# Aux_Power_Board.net
KiCad netlist of a schematic drawn in EAGLE
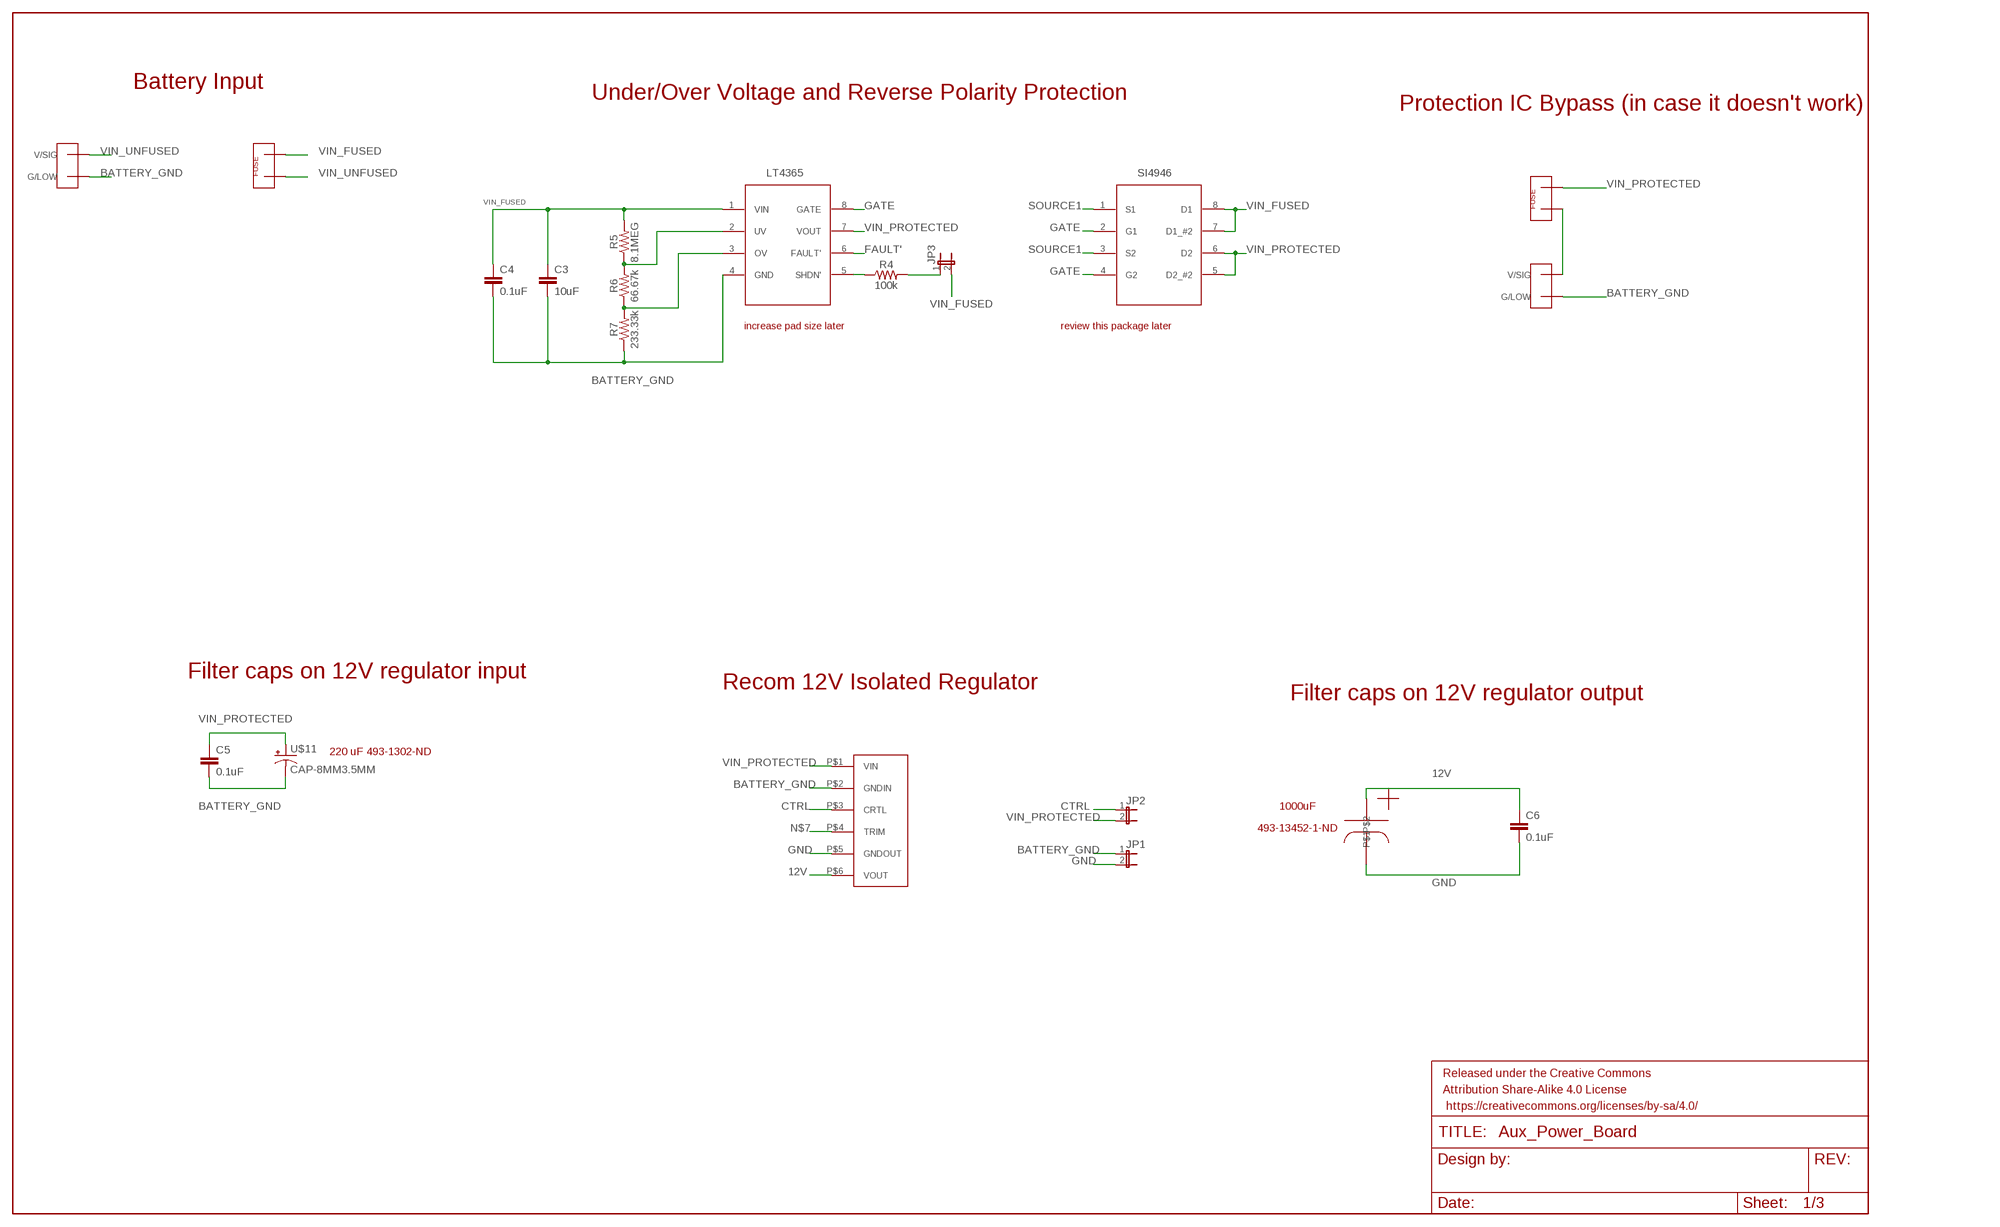
[diagram p0: schematic, sheet 1]
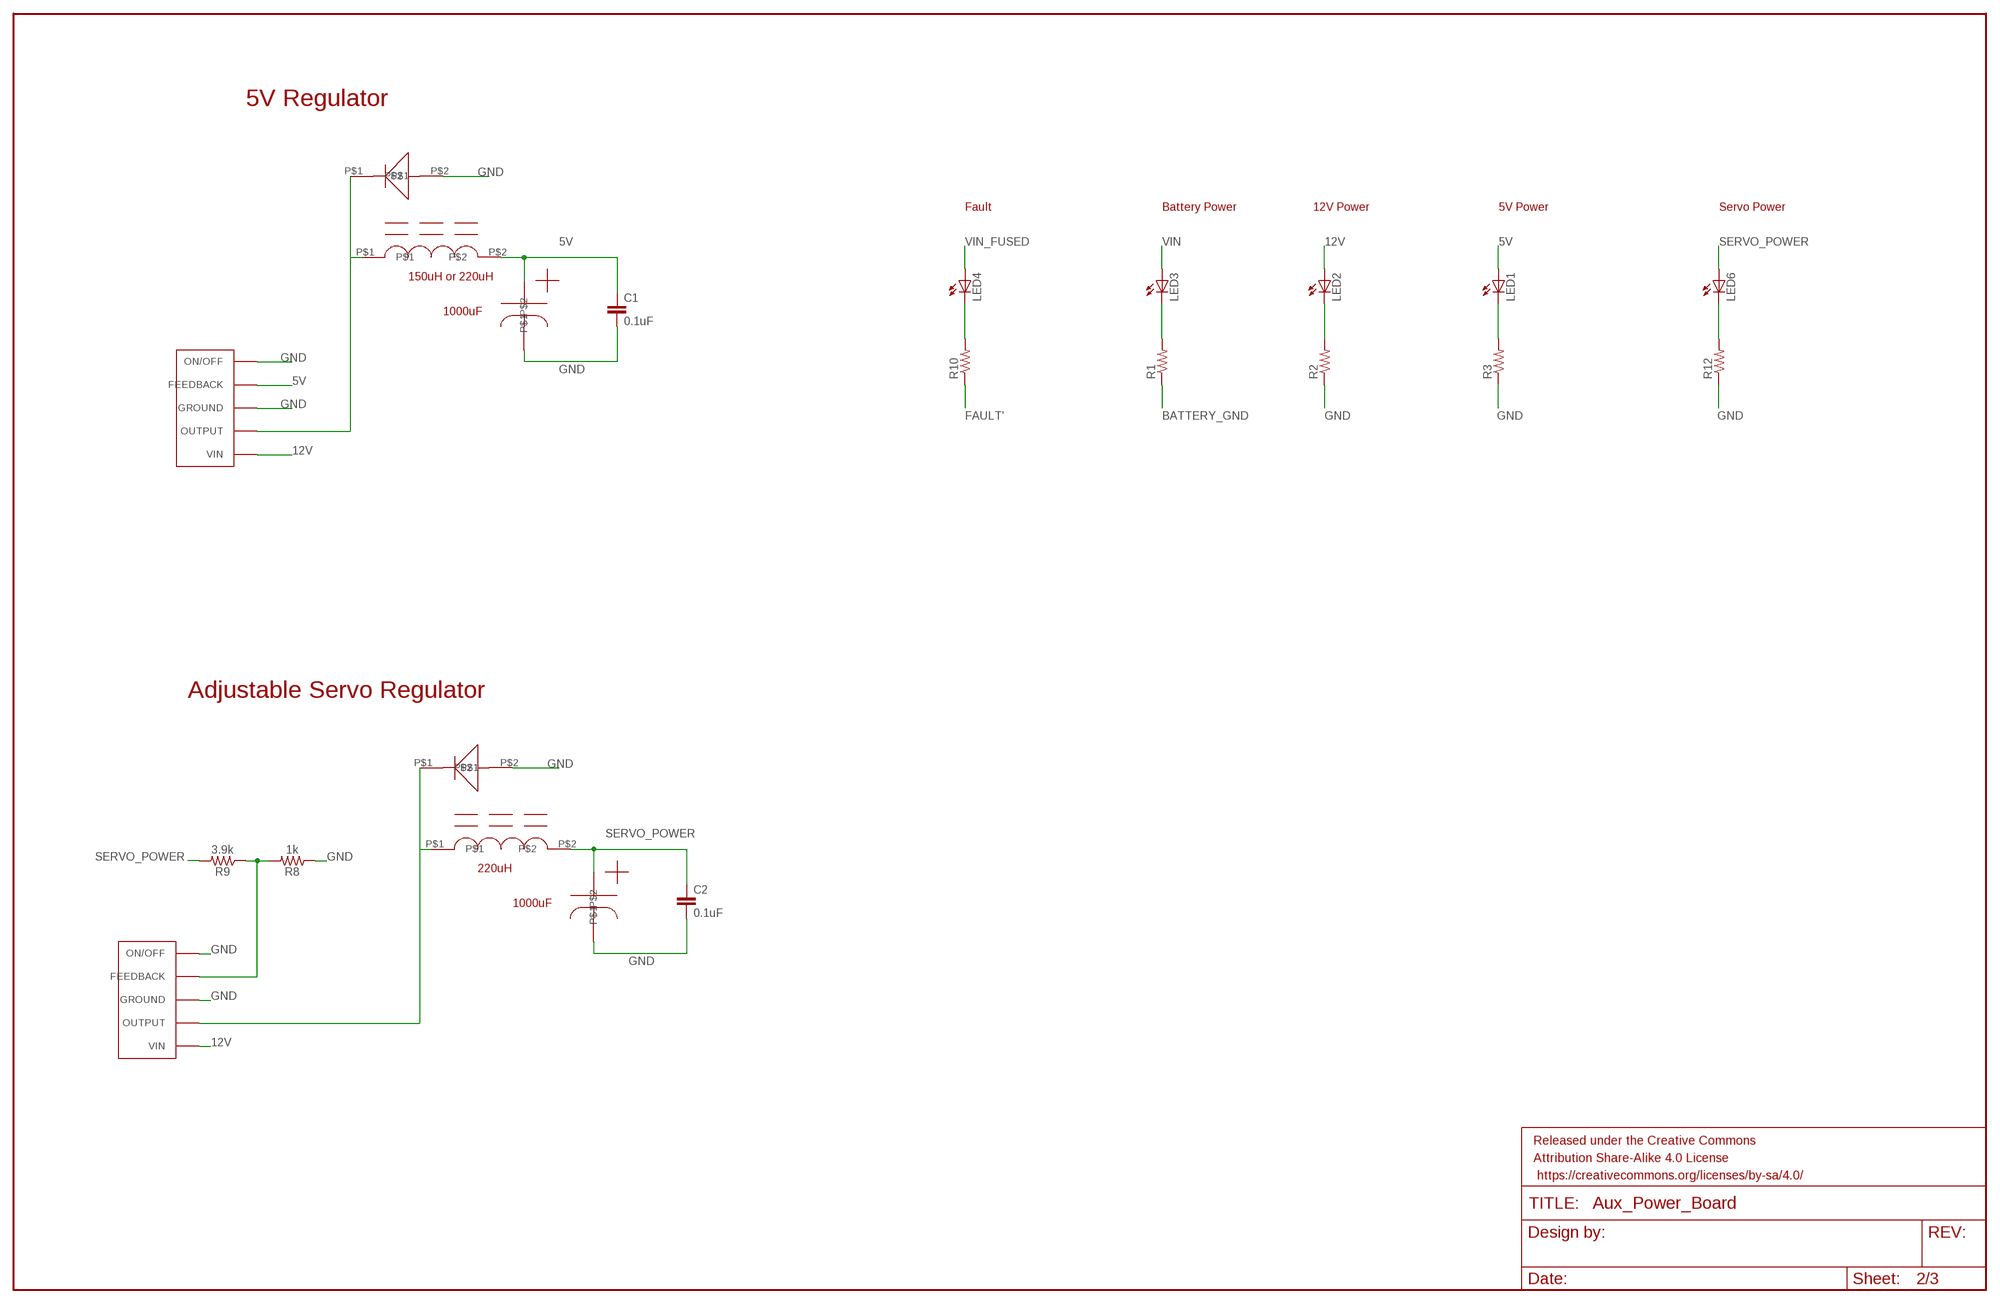
[diagram p1: schematic, sheet 2]
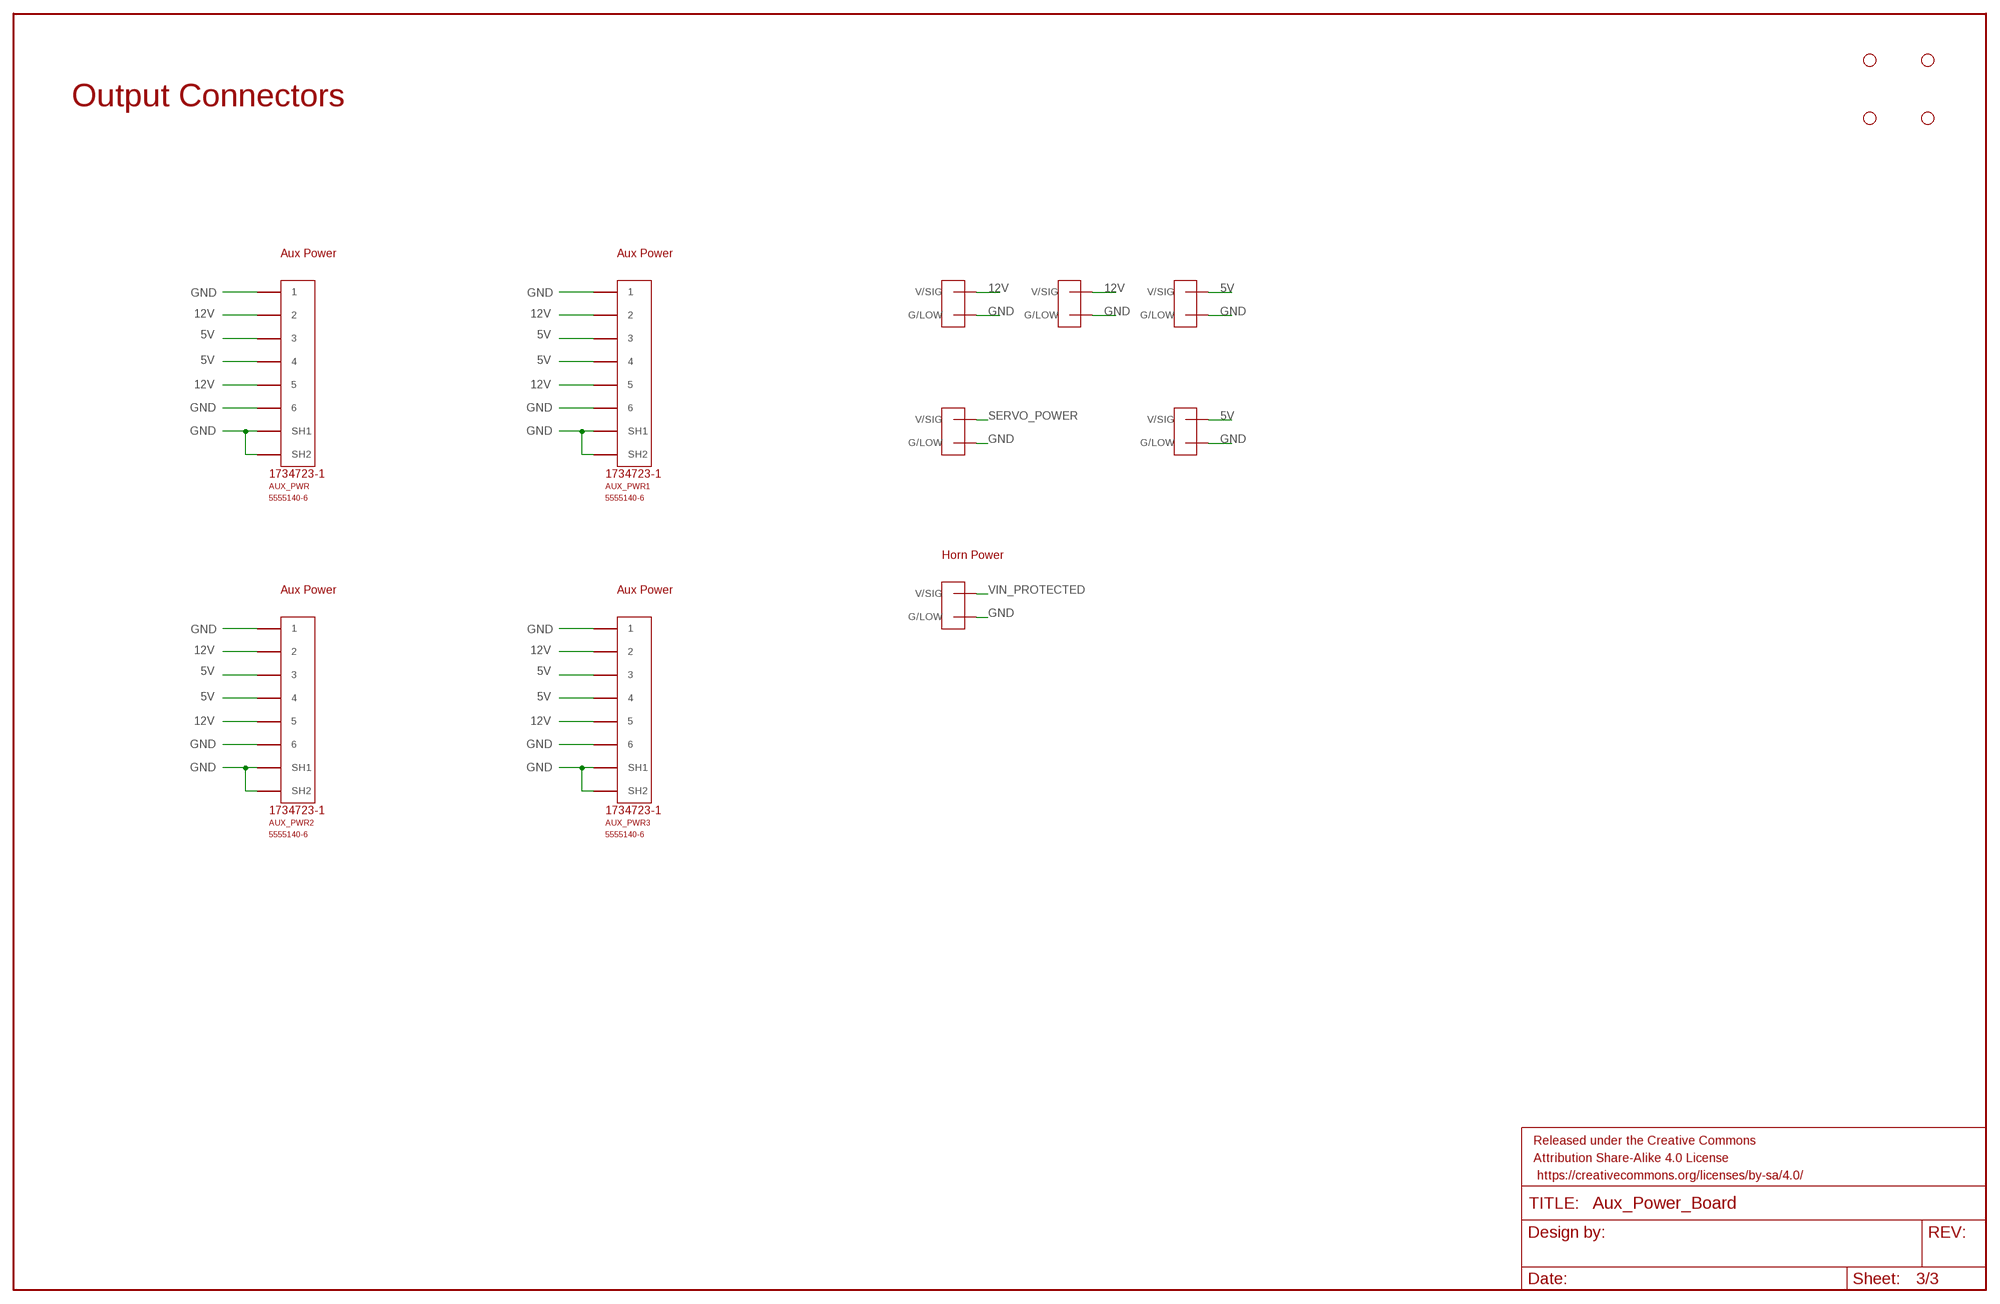
[diagram p2: schematic, sheet 3]

(export (version "E")
  (design (tool "Eeschema 10.0.6"))
  (components
    (comp (ref "AUX_PWR")
      (value "5555140-6")
      (footprint "eagle-import:1734723-1_RJ11")
      (libsource (lib "eagle-import") (part "5555140-6"))
    )
    (comp (ref "AUX_PWR1")
      (value "5555140-6")
      (footprint "eagle-import:1734723-1_RJ11")
      (libsource (lib "eagle-import") (part "5555140-6"))
    )
    (comp (ref "AUX_PWR2")
      (value "5555140-6")
      (footprint "eagle-import:1734723-1_RJ11")
      (libsource (lib "eagle-import") (part "5555140-6"))
    )
    (comp (ref "AUX_PWR3")
      (value "5555140-6")
      (footprint "eagle-import:1734723-1_RJ11")
      (libsource (lib "eagle-import") (part "5555140-6"))
    )
    (comp (ref "FRAME4")
      (value "FRAME-LEDGER")
      (footprint "eagle-import:CREATIVE_COMMONS")
      (libsource (lib "eagle-import") (part "FRAME-LEDGER"))
    )
    (comp (ref "H1")
      (value "STAND-OFF")
      (footprint "eagle-import:STAND-OFF")
      (libsource (lib "eagle-import") (part "STAND-OFF"))
    )
    (comp (ref "H2")
      (value "STAND-OFF")
      (footprint "eagle-import:STAND-OFF")
      (libsource (lib "eagle-import") (part "STAND-OFF"))
    )
    (comp (ref "H3")
      (value "STAND-OFF")
      (footprint "eagle-import:STAND-OFF")
      (libsource (lib "eagle-import") (part "STAND-OFF"))
    )
    (comp (ref "H4")
      (value "STAND-OFF")
      (footprint "eagle-import:STAND-OFF")
      (libsource (lib "eagle-import") (part "STAND-OFF"))
    )
    (comp (ref "U$1")
      (value "TE770966")
      (footprint "eagle-import:2X1-MATE-N-LOCK")
      (libsource (lib "eagle-import") (part "TE770966"))
    )
    (comp (ref "U$2")
      (value "TE770966")
      (footprint "eagle-import:2X1-MATE-N-LOCK")
      (libsource (lib "eagle-import") (part "TE770966"))
    )
    (comp (ref "U$3")
      (value "TE770966")
      (footprint "eagle-import:2X1-MATE-N-LOCK")
      (libsource (lib "eagle-import") (part "TE770966"))
    )
    (comp (ref "U$15")
      (value "TE770966")
      (footprint "eagle-import:2X1-MATE-N-LOCK")
      (libsource (lib "eagle-import") (part "TE770966"))
    )
    (comp (ref "U$26")
      (value "TE770966")
      (footprint "eagle-import:2X1-MATE-N-LOCK")
      (libsource (lib "eagle-import") (part "TE770966"))
    )
    (comp (ref "U$27")
      (value "TE770966")
      (footprint "eagle-import:2X1-MATE-N-LOCK")
      (libsource (lib "eagle-import") (part "TE770966"))
    )
    (comp (ref "C3")
      (value "10uF")
      (footprint "eagle-import:0805")
      (libsource (lib "eagle-import") (part "1.0UF-0805-25V-10%"))
    )
    (comp (ref "C4")
      (value "0.1uF")
      (footprint "eagle-import:0805")
      (libsource (lib "eagle-import") (part "1.0UF-0805-25V-10%"))
    )
    (comp (ref "C5")
      (value "0.1uF")
      (footprint "eagle-import:0805")
      (libsource (lib "eagle-import") (part "1.0UF-0805-25V-10%"))
    )
    (comp (ref "C6")
      (value "0.1uF")
      (footprint "eagle-import:0805")
      (libsource (lib "eagle-import") (part "1.0UF-0805-25V-10%"))
    )
    (comp (ref "FRAME2")
      (value "FRAME-LEDGER")
      (footprint "eagle-import:CREATIVE_COMMONS")
      (libsource (lib "eagle-import") (part "FRAME-LEDGER"))
    )
    (comp (ref "JP1")
      (value "JP1E")
      (footprint "eagle-import:JP1")
      (libsource (lib "eagle-import") (part "JP1E"))
    )
    (comp (ref "JP2")
      (value "JP1E")
      (footprint "eagle-import:JP1")
      (libsource (lib "eagle-import") (part "JP1E"))
    )
    (comp (ref "JP3")
      (value "JP1E")
      (footprint "eagle-import:JP1")
      (libsource (lib "eagle-import") (part "JP1E"))
    )
    (comp (ref "R4")
      (value "100k")
      (footprint "eagle-import:0805")
      (libsource (lib "eagle-import") (part "0.22OHM-0805-1/4W-1%"))
    )
    (comp (ref "R5")
      (value "8.1MEG")
      (footprint "eagle-import:0805")
      (libsource (lib "eagle-import") (part "0.22OHM-0805-1/4W-1%"))
    )
    (comp (ref "R6")
      (value "66.67k")
      (footprint "eagle-import:0805")
      (libsource (lib "eagle-import") (part "0.22OHM-0805-1/4W-1%"))
    )
    (comp (ref "R7")
      (value "233.33k")
      (footprint "eagle-import:0805")
      (libsource (lib "eagle-import") (part "0.22OHM-0805-1/4W-1%"))
    )
    (comp (ref "U$5")
      (value "LT4365")
      (footprint "eagle-import:TSOT-23_TS8")
      (libsource (lib "eagle-import") (part "LT4365"))
    )
    (comp (ref "U$6")
      (value "SI4946")
      (footprint "eagle-import:SOIC127P600X175-8N")
      (libsource (lib "eagle-import") (part "SI4946"))
    )
    (comp (ref "U$11")
      (value "CAP-8MM3.5MM")
      (footprint "eagle-import:CAP-8MM_3.5MM")
      (libsource (lib "eagle-import") (part "CAP-8MM3.5MM"))
    )
    (comp (ref "U$12")
      (value "RPA60-2412SFW_P")
      (footprint "eagle-import:RPA60-2412SFW_P")
      (libsource (lib "eagle-import") (part "RPA60-2412SFW_P"))
    )
    (comp (ref "U$13")
      (value "FUSEMINI-BLADE")
      (footprint "eagle-import:MINI-BLADE-FUSE")
      (libsource (lib "eagle-import") (part "FUSEMINI-BLADE"))
    )
    (comp (ref "U$14")
      (value "TE770966")
      (footprint "eagle-import:2X1-MATE-N-LOCK")
      (libsource (lib "eagle-import") (part "TE770966"))
    )
    (comp (ref "U$20")
      (value "FUSEMINI-BLADE")
      (footprint "eagle-import:MINI-BLADE-FUSE")
      (libsource (lib "eagle-import") (part "FUSEMINI-BLADE"))
    )
    (comp (ref "U$21")
      (value "TE770966")
      (footprint "eagle-import:2X1-MATE-N-LOCK")
      (libsource (lib "eagle-import") (part "TE770966"))
    )
    (comp (ref "U$22")
      (value "CAPESK108M025AH4EA")
      (footprint "eagle-import:ESK108M025AH4EA")
      (libsource (lib "eagle-import") (part "CAPESK108M025AH4EA"))
    )
    (comp (ref "C1")
      (value "0.1uF")
      (footprint "eagle-import:0805")
      (libsource (lib "eagle-import") (part "1.0UF-0805-25V-10%"))
    )
    (comp (ref "C2")
      (value "0.1uF")
      (footprint "eagle-import:0805")
      (libsource (lib "eagle-import") (part "1.0UF-0805-25V-10%"))
    )
    (comp (ref "FRAME1")
      (value "FRAME-LEDGER")
      (footprint "eagle-import:CREATIVE_COMMONS")
      (libsource (lib "eagle-import") (part "FRAME-LEDGER"))
    )
    (comp (ref "LED1")
      (value "LEDCHIP-LED0805")
      (footprint "eagle-import:CHIP-LED0805")
      (libsource (lib "eagle-import") (part "LEDCHIP-LED0805"))
    )
    (comp (ref "LED2")
      (value "LEDCHIP-LED0805")
      (footprint "eagle-import:CHIP-LED0805")
      (libsource (lib "eagle-import") (part "LEDCHIP-LED0805"))
    )
    (comp (ref "LED3")
      (value "LEDCHIP-LED0805")
      (footprint "eagle-import:CHIP-LED0805")
      (libsource (lib "eagle-import") (part "LEDCHIP-LED0805"))
    )
    (comp (ref "LED4")
      (value "LEDCHIP-LED0805")
      (footprint "eagle-import:CHIP-LED0805")
      (libsource (lib "eagle-import") (part "LEDCHIP-LED0805"))
    )
    (comp (ref "LED6")
      (value "LEDCHIP-LED0805")
      (footprint "eagle-import:CHIP-LED0805")
      (libsource (lib "eagle-import") (part "LEDCHIP-LED0805"))
    )
    (comp (ref "R1")
      (value "R-US_M0805")
      (footprint "eagle-import:M0805")
      (libsource (lib "eagle-import") (part "R-US_M0805"))
    )
    (comp (ref "R2")
      (value "R-US_M0805")
      (footprint "eagle-import:M0805")
      (libsource (lib "eagle-import") (part "R-US_M0805"))
    )
    (comp (ref "R3")
      (value "R-US_M0805")
      (footprint "eagle-import:M0805")
      (libsource (lib "eagle-import") (part "R-US_M0805"))
    )
    (comp (ref "R8")
      (value "1k")
      (footprint "eagle-import:0805")
      (libsource (lib "eagle-import") (part "0.22OHM-0805-1/4W-1%"))
    )
    (comp (ref "R9")
      (value "3.9k")
      (footprint "eagle-import:0805")
      (libsource (lib "eagle-import") (part "0.22OHM-0805-1/4W-1%"))
    )
    (comp (ref "R10")
      (value "R-US_M0805")
      (footprint "eagle-import:M0805")
      (libsource (lib "eagle-import") (part "R-US_M0805"))
    )
    (comp (ref "R12")
      (value "R-US_M0805")
      (footprint "eagle-import:M0805")
      (libsource (lib "eagle-import") (part "R-US_M0805"))
    )
    (comp (ref "U$4")
      (value "MBR360GOS")
      (footprint "eagle-import:MBR360GOS")
      (libsource (lib "eagle-import") (part "MBR360GOS"))
    )
    (comp (ref "U$7")
      (value "LM2576")
      (footprint "eagle-import:D2PAK-5")
      (libsource (lib "eagle-import") (part "LM2576"))
    )
    (comp (ref "U$8")
      (value "MBR360GOS")
      (footprint "eagle-import:MBR360GOS")
      (libsource (lib "eagle-import") (part "MBR360GOS"))
    )
    (comp (ref "U$9")
      (value "CAPESK108M025AH4EA")
      (footprint "eagle-import:ESK108M025AH4EA")
      (libsource (lib "eagle-import") (part "CAPESK108M025AH4EA"))
    )
    (comp (ref "U$10")
      (value "M1418-ND")
      (footprint "eagle-import:M1418-ND")
      (libsource (lib "eagle-import") (part "M1418-ND"))
    )
    (comp (ref "U$23")
      (value "LM2576")
      (footprint "eagle-import:D2PAK-5")
      (libsource (lib "eagle-import") (part "LM2576"))
    )
    (comp (ref "U$24")
      (value "CAPESK108M025AH4EA")
      (footprint "eagle-import:ESK108M025AH4EA")
      (libsource (lib "eagle-import") (part "CAPESK108M025AH4EA"))
    )
    (comp (ref "U$25")
      (value "M1418-ND")
      (footprint "eagle-import:M1418-ND")
      (libsource (lib "eagle-import") (part "M1418-ND"))
    )
  )
  (nets
    (net (code "1") (name "5V") (class "Default")
      (node (ref "AUX_PWR") (pin "3") (pinfunction "3_3") (pintype "bidirectional"))
      (node (ref "AUX_PWR") (pin "4") (pinfunction "4_4") (pintype "bidirectional"))
      (node (ref "AUX_PWR1") (pin "3") (pinfunction "3_3") (pintype "bidirectional"))
      (node (ref "AUX_PWR1") (pin "4") (pinfunction "4_4") (pintype "bidirectional"))
      (node (ref "AUX_PWR2") (pin "3") (pinfunction "3_3") (pintype "bidirectional"))
      (node (ref "AUX_PWR2") (pin "4") (pinfunction "4_4") (pintype "bidirectional"))
      (node (ref "AUX_PWR3") (pin "3") (pinfunction "3_3") (pintype "bidirectional"))
      (node (ref "AUX_PWR3") (pin "4") (pinfunction "4_4") (pintype "bidirectional"))
      (node (ref "C1") (pin "1") (pinfunction "1_1") (pintype "passive"))
      (node (ref "LED1") (pin "A") (pinfunction "A_A") (pintype "passive"))
      (node (ref "U$10") (pin "P$2") (pinfunction "P$2_P$2") (pintype "bidirectional"))
      (node (ref "U$27") (pin "CIRCUIT1") (pinfunction "V/SIG_CIRCUIT1") (pintype "bidirectional"))
      (node (ref "U$3") (pin "CIRCUIT1") (pinfunction "V/SIG_CIRCUIT1") (pintype "bidirectional"))
      (node (ref "U$7") (pin "4") (pinfunction "FEEDBACK_4") (pintype "bidirectional"))
      (node (ref "U$9") (pin "P$1") (pinfunction "P$1_P$1") (pintype "bidirectional"))
    )
    (net (code "2") (name "12V") (class "Default")
      (node (ref "AUX_PWR") (pin "2") (pinfunction "2_2") (pintype "bidirectional"))
      (node (ref "AUX_PWR") (pin "5") (pinfunction "5_5") (pintype "bidirectional"))
      (node (ref "AUX_PWR1") (pin "2") (pinfunction "2_2") (pintype "bidirectional"))
      (node (ref "AUX_PWR1") (pin "5") (pinfunction "5_5") (pintype "bidirectional"))
      (node (ref "AUX_PWR2") (pin "2") (pinfunction "2_2") (pintype "bidirectional"))
      (node (ref "AUX_PWR2") (pin "5") (pinfunction "5_5") (pintype "bidirectional"))
      (node (ref "AUX_PWR3") (pin "2") (pinfunction "2_2") (pintype "bidirectional"))
      (node (ref "AUX_PWR3") (pin "5") (pinfunction "5_5") (pintype "bidirectional"))
      (node (ref "C6") (pin "1") (pinfunction "1_1") (pintype "passive"))
      (node (ref "LED2") (pin "A") (pinfunction "A_A") (pintype "passive"))
      (node (ref "U$1") (pin "CIRCUIT1") (pinfunction "V/SIG_CIRCUIT1") (pintype "bidirectional"))
      (node (ref "U$12") (pin "P$6") (pinfunction "VOUT_P$6") (pintype "bidirectional"))
      (node (ref "U$2") (pin "CIRCUIT1") (pinfunction "V/SIG_CIRCUIT1") (pintype "bidirectional"))
      (node (ref "U$22") (pin "P$1") (pinfunction "P$1_P$1") (pintype "bidirectional"))
      (node (ref "U$23") (pin "1") (pinfunction "VIN_1") (pintype "bidirectional"))
      (node (ref "U$7") (pin "1") (pinfunction "VIN_1") (pintype "bidirectional"))
    )
    (net (code "3") (name "BATTERY_GND") (class "Default")
      (node (ref "C3") (pin "2") (pinfunction "2_2") (pintype "passive"))
      (node (ref "C4") (pin "2") (pinfunction "2_2") (pintype "passive"))
      (node (ref "C5") (pin "2") (pinfunction "2_2") (pintype "passive"))
      (node (ref "JP1") (pin "1") (pinfunction "1_1") (pintype "passive"))
      (node (ref "R1") (pin "1") (pinfunction "1_1") (pintype "passive"))
      (node (ref "R7") (pin "1") (pinfunction "1_1") (pintype "passive"))
      (node (ref "U$11") (pin "P$2") (pinfunction "-_P$2") (pintype "passive"))
      (node (ref "U$12") (pin "P$2") (pinfunction "GNDIN_P$2") (pintype "bidirectional"))
      (node (ref "U$14") (pin "CIRCUIT2") (pinfunction "G/LOW_CIRCUIT2") (pintype "bidirectional"))
      (node (ref "U$21") (pin "CIRCUIT2") (pinfunction "G/LOW_CIRCUIT2") (pintype "bidirectional"))
      (node (ref "U$5") (pin "4") (pinfunction "GND_4") (pintype "bidirectional"))
    )
    (net (code "4") (name "CTRL") (class "Default")
      (node (ref "JP2") (pin "1") (pinfunction "1_1") (pintype "passive"))
      (node (ref "U$12") (pin "P$3") (pinfunction "CRTL_P$3") (pintype "bidirectional"))
    )
    (net (code "5") (name "FAULT'") (class "Default")
      (node (ref "R10") (pin "1") (pinfunction "1_1") (pintype "passive"))
      (node (ref "U$5") (pin "6") (pinfunction "FAULT'_6") (pintype "bidirectional"))
    )
    (net (code "6") (name "GATE") (class "Default")
      (node (ref "U$5") (pin "8") (pinfunction "GATE_8") (pintype "bidirectional"))
      (node (ref "U$6") (pin "2") (pinfunction "G1_2") (pintype "bidirectional"))
      (node (ref "U$6") (pin "4") (pinfunction "G2_4") (pintype "bidirectional"))
    )
    (net (code "7") (name "GND") (class "Default")
      (node (ref "AUX_PWR") (pin "1") (pinfunction "1_1") (pintype "bidirectional"))
      (node (ref "AUX_PWR") (pin "6") (pinfunction "6_6") (pintype "bidirectional"))
      (node (ref "AUX_PWR") (pin "SH1") (pinfunction "SH1_SH1") (pintype "bidirectional"))
      (node (ref "AUX_PWR") (pin "SH2") (pinfunction "SH2_SH2") (pintype "bidirectional"))
      (node (ref "AUX_PWR1") (pin "1") (pinfunction "1_1") (pintype "bidirectional"))
      (node (ref "AUX_PWR1") (pin "6") (pinfunction "6_6") (pintype "bidirectional"))
      (node (ref "AUX_PWR1") (pin "SH1") (pinfunction "SH1_SH1") (pintype "bidirectional"))
      (node (ref "AUX_PWR1") (pin "SH2") (pinfunction "SH2_SH2") (pintype "bidirectional"))
      (node (ref "AUX_PWR2") (pin "1") (pinfunction "1_1") (pintype "bidirectional"))
      (node (ref "AUX_PWR2") (pin "6") (pinfunction "6_6") (pintype "bidirectional"))
      (node (ref "AUX_PWR2") (pin "SH1") (pinfunction "SH1_SH1") (pintype "bidirectional"))
      (node (ref "AUX_PWR2") (pin "SH2") (pinfunction "SH2_SH2") (pintype "bidirectional"))
      (node (ref "AUX_PWR3") (pin "1") (pinfunction "1_1") (pintype "bidirectional"))
      (node (ref "AUX_PWR3") (pin "6") (pinfunction "6_6") (pintype "bidirectional"))
      (node (ref "AUX_PWR3") (pin "SH1") (pinfunction "SH1_SH1") (pintype "bidirectional"))
      (node (ref "AUX_PWR3") (pin "SH2") (pinfunction "SH2_SH2") (pintype "bidirectional"))
      (node (ref "C1") (pin "2") (pinfunction "2_2") (pintype "passive"))
      (node (ref "C2") (pin "2") (pinfunction "2_2") (pintype "passive"))
      (node (ref "C6") (pin "2") (pinfunction "2_2") (pintype "passive"))
      (node (ref "JP1") (pin "2") (pinfunction "2_2") (pintype "passive"))
      (node (ref "R12") (pin "1") (pinfunction "1_1") (pintype "passive"))
      (node (ref "R2") (pin "1") (pinfunction "1_1") (pintype "passive"))
      (node (ref "R3") (pin "1") (pinfunction "1_1") (pintype "passive"))
      (node (ref "R8") (pin "1") (pinfunction "1_1") (pintype "passive"))
      (node (ref "U$1") (pin "CIRCUIT2") (pinfunction "G/LOW_CIRCUIT2") (pintype "bidirectional"))
      (node (ref "U$12") (pin "P$5") (pinfunction "GNDOUT_P$5") (pintype "bidirectional"))
      (node (ref "U$15") (pin "CIRCUIT2") (pinfunction "G/LOW_CIRCUIT2") (pintype "bidirectional"))
      (node (ref "U$2") (pin "CIRCUIT2") (pinfunction "G/LOW_CIRCUIT2") (pintype "bidirectional"))
      (node (ref "U$22") (pin "P$2") (pinfunction "P$2_P$2") (pintype "bidirectional"))
      (node (ref "U$23") (pin "3") (pinfunction "GROUND_3") (pintype "bidirectional"))
      (node (ref "U$23") (pin "5") (pinfunction "ON/OFF_5") (pintype "bidirectional"))
      (node (ref "U$23") (pin "GROUND") (pinfunction "GROUND_GROUND") (pintype "bidirectional"))
      (node (ref "U$24") (pin "P$2") (pinfunction "P$2_P$2") (pintype "bidirectional"))
      (node (ref "U$26") (pin "CIRCUIT2") (pinfunction "G/LOW_CIRCUIT2") (pintype "bidirectional"))
      (node (ref "U$27") (pin "CIRCUIT2") (pinfunction "G/LOW_CIRCUIT2") (pintype "bidirectional"))
      (node (ref "U$3") (pin "CIRCUIT2") (pinfunction "G/LOW_CIRCUIT2") (pintype "bidirectional"))
      (node (ref "U$4") (pin "P$2") (pinfunction "P$1_P$2") (pintype "bidirectional"))
      (node (ref "U$7") (pin "3") (pinfunction "GROUND_3") (pintype "bidirectional"))
      (node (ref "U$7") (pin "5") (pinfunction "ON/OFF_5") (pintype "bidirectional"))
      (node (ref "U$7") (pin "GROUND") (pinfunction "GROUND_GROUND") (pintype "bidirectional"))
      (node (ref "U$8") (pin "P$2") (pinfunction "P$1_P$2") (pintype "bidirectional"))
      (node (ref "U$9") (pin "P$2") (pinfunction "P$2_P$2") (pintype "bidirectional"))
    )
    (net (code "8") (name "N$7") (class "Default")
      (node (ref "U$12") (pin "P$4") (pinfunction "TRIM_P$4") (pintype "bidirectional"))
    )
    (net (code "9") (name "Net-(JP3-Pad1)") (class "Default")
      (node (ref "JP3") (pin "1") (pinfunction "1_1") (pintype "passive"))
      (node (ref "R4") (pin "2") (pinfunction "2_2") (pintype "passive"))
    )
    (net (code "10") (name "Net-(LED1-PadC)") (class "Default")
      (node (ref "LED1") (pin "C") (pinfunction "C_C") (pintype "passive"))
      (node (ref "R3") (pin "2") (pinfunction "2_2") (pintype "passive"))
    )
    (net (code "11") (name "Net-(LED2-PadC)") (class "Default")
      (node (ref "LED2") (pin "C") (pinfunction "C_C") (pintype "passive"))
      (node (ref "R2") (pin "2") (pinfunction "2_2") (pintype "passive"))
    )
    (net (code "12") (name "Net-(LED3-PadC)") (class "Default")
      (node (ref "LED3") (pin "C") (pinfunction "C_C") (pintype "passive"))
      (node (ref "R1") (pin "2") (pinfunction "2_2") (pintype "passive"))
    )
    (net (code "13") (name "Net-(LED4-PadC)") (class "Default")
      (node (ref "LED4") (pin "C") (pinfunction "C_C") (pintype "passive"))
      (node (ref "R10") (pin "2") (pinfunction "2_2") (pintype "passive"))
    )
    (net (code "14") (name "Net-(LED6-PadC)") (class "Default")
      (node (ref "LED6") (pin "C") (pinfunction "C_C") (pintype "passive"))
      (node (ref "R12") (pin "2") (pinfunction "2_2") (pintype "passive"))
    )
    (net (code "15") (name "Net-(U$4-P$2)") (class "Default")
      (node (ref "U$10") (pin "P$1") (pinfunction "P$1_P$1") (pintype "bidirectional"))
      (node (ref "U$4") (pin "P$1") (pinfunction "P$2_P$1") (pintype "bidirectional"))
      (node (ref "U$7") (pin "2") (pinfunction "OUTPUT_2") (pintype "bidirectional"))
    )
    (net (code "16") (name "Net-(U$5-OV)") (class "Default")
      (node (ref "R6") (pin "1") (pinfunction "1_1") (pintype "passive"))
      (node (ref "R7") (pin "2") (pinfunction "2_2") (pintype "passive"))
      (node (ref "U$5") (pin "3") (pinfunction "OV_3") (pintype "bidirectional"))
    )
    (net (code "17") (name "Net-(U$5-SHDN')") (class "Default")
      (node (ref "R4") (pin "1") (pinfunction "1_1") (pintype "passive"))
      (node (ref "U$5") (pin "5") (pinfunction "SHDN'_5") (pintype "bidirectional"))
    )
    (net (code "18") (name "Net-(U$5-UV)") (class "Default")
      (node (ref "R5") (pin "1") (pinfunction "1_1") (pintype "passive"))
      (node (ref "R6") (pin "2") (pinfunction "2_2") (pintype "passive"))
      (node (ref "U$5") (pin "2") (pinfunction "UV_2") (pintype "bidirectional"))
    )
    (net (code "19") (name "Net-(U$21-V{slash}SIG)") (class "Default")
      (node (ref "U$20") (pin "IN") (pinfunction "IN_IN") (pintype "bidirectional"))
      (node (ref "U$21") (pin "CIRCUIT1") (pinfunction "V/SIG_CIRCUIT1") (pintype "bidirectional"))
    )
    (net (code "20") (name "Net-(U$23-FEEDBACK)") (class "Default")
      (node (ref "R8") (pin "2") (pinfunction "2_2") (pintype "passive"))
      (node (ref "R9") (pin "1") (pinfunction "1_1") (pintype "passive"))
      (node (ref "U$23") (pin "4") (pinfunction "FEEDBACK_4") (pintype "bidirectional"))
    )
    (net (code "21") (name "Net-(U$23-OUTPUT)") (class "Default")
      (node (ref "U$23") (pin "2") (pinfunction "OUTPUT_2") (pintype "bidirectional"))
      (node (ref "U$25") (pin "P$1") (pinfunction "P$1_P$1") (pintype "bidirectional"))
      (node (ref "U$8") (pin "P$1") (pinfunction "P$2_P$1") (pintype "bidirectional"))
    )
    (net (code "22") (name "SERVO_POWER") (class "Default")
      (node (ref "C2") (pin "1") (pinfunction "1_1") (pintype "passive"))
      (node (ref "LED6") (pin "A") (pinfunction "A_A") (pintype "passive"))
      (node (ref "R9") (pin "2") (pinfunction "2_2") (pintype "passive"))
      (node (ref "U$24") (pin "P$1") (pinfunction "P$1_P$1") (pintype "bidirectional"))
      (node (ref "U$25") (pin "P$2") (pinfunction "P$2_P$2") (pintype "bidirectional"))
      (node (ref "U$26") (pin "CIRCUIT1") (pinfunction "V/SIG_CIRCUIT1") (pintype "bidirectional"))
    )
    (net (code "23") (name "SOURCE1") (class "Default")
      (node (ref "U$6") (pin "1") (pinfunction "S1_1") (pintype "bidirectional"))
      (node (ref "U$6") (pin "3") (pinfunction "S2_3") (pintype "bidirectional"))
    )
    (net (code "24") (name "VIN") (class "Default")
      (node (ref "LED3") (pin "A") (pinfunction "A_A") (pintype "passive"))
    )
    (net (code "25") (name "VIN_FUSED") (class "Default")
      (node (ref "C3") (pin "1") (pinfunction "1_1") (pintype "passive"))
      (node (ref "C4") (pin "1") (pinfunction "1_1") (pintype "passive"))
      (node (ref "JP3") (pin "2") (pinfunction "2_2") (pintype "passive"))
      (node (ref "LED4") (pin "A") (pinfunction "A_A") (pintype "passive"))
      (node (ref "R5") (pin "2") (pinfunction "2_2") (pintype "passive"))
      (node (ref "U$13") (pin "OUT") (pinfunction "OUT_OUT") (pintype "bidirectional"))
      (node (ref "U$5") (pin "1") (pinfunction "VIN_1") (pintype "bidirectional"))
      (node (ref "U$6") (pin "7") (pinfunction "D1_#2_7") (pintype "bidirectional"))
      (node (ref "U$6") (pin "8") (pinfunction "D1_8") (pintype "bidirectional"))
    )
    (net (code "26") (name "VIN_PROTECTED") (class "Default")
      (node (ref "C5") (pin "1") (pinfunction "1_1") (pintype "passive"))
      (node (ref "JP2") (pin "2") (pinfunction "2_2") (pintype "passive"))
      (node (ref "U$11") (pin "P$1") (pinfunction "+_P$1") (pintype "passive"))
      (node (ref "U$12") (pin "P$1") (pinfunction "VIN_P$1") (pintype "bidirectional"))
      (node (ref "U$15") (pin "CIRCUIT1") (pinfunction "V/SIG_CIRCUIT1") (pintype "bidirectional"))
      (node (ref "U$20") (pin "OUT") (pinfunction "OUT_OUT") (pintype "bidirectional"))
      (node (ref "U$5") (pin "7") (pinfunction "VOUT_7") (pintype "bidirectional"))
      (node (ref "U$6") (pin "5") (pinfunction "D2_#2_5") (pintype "bidirectional"))
      (node (ref "U$6") (pin "6") (pinfunction "D2_6") (pintype "bidirectional"))
    )
    (net (code "27") (name "VIN_UNFUSED") (class "Default")
      (node (ref "U$13") (pin "IN") (pinfunction "IN_IN") (pintype "bidirectional"))
      (node (ref "U$14") (pin "CIRCUIT1") (pinfunction "V/SIG_CIRCUIT1") (pintype "bidirectional"))
    )
  )
)
